# attiny_cortana.net
KiCad netlist of a schematic drawn in EAGLE
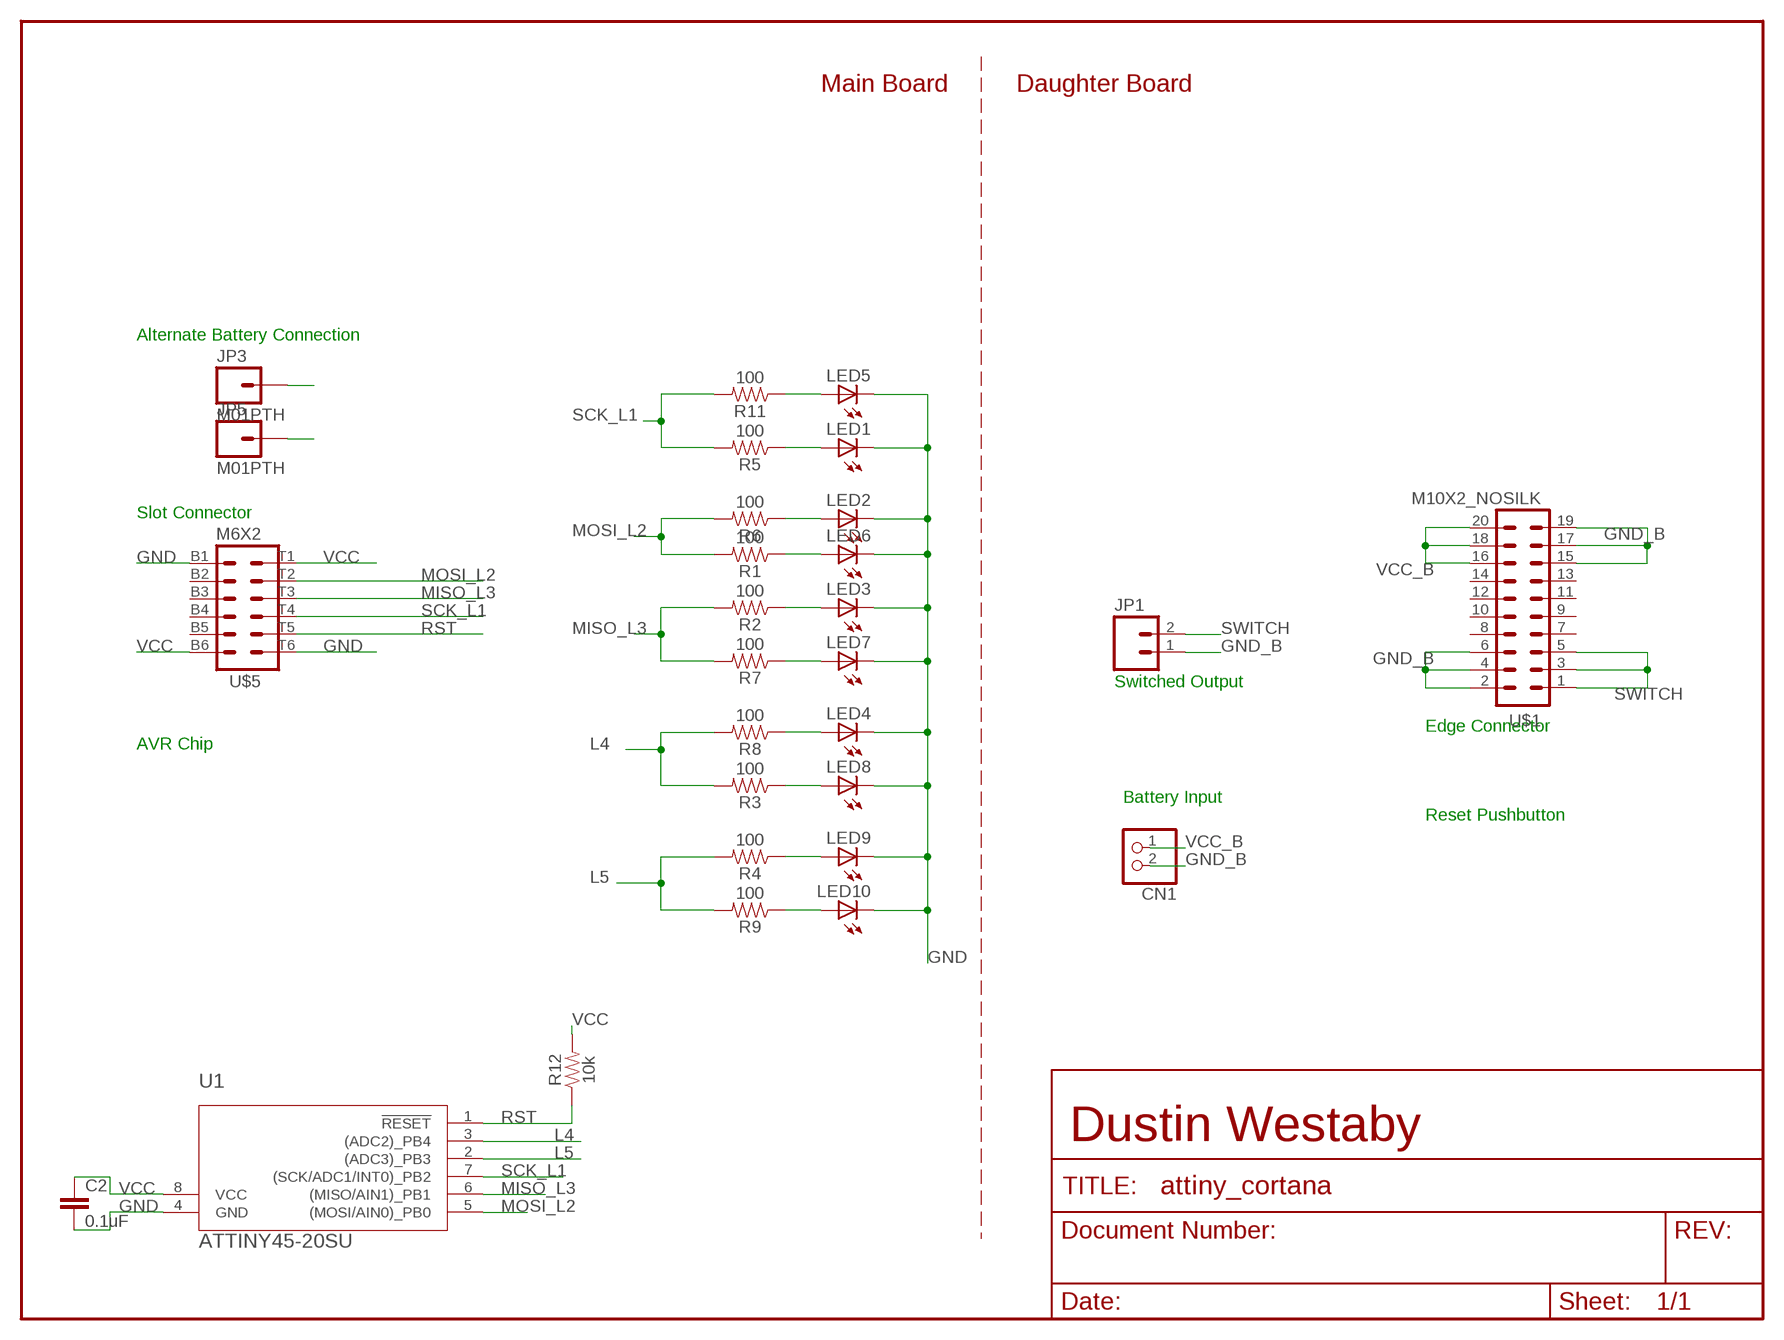
[diagram p0: schematic, sheet 1]

(export (version "E")
  (design (tool "Eeschema 10.0.6"))
  (components
    (comp (ref "C2")
      (value "0.1uF")
      (footprint "eagle-import:0402-TIGHT")
      (libsource (lib "eagle-import") (part "0.1UF-0402T-16V-10%"))
    )
    (comp (ref "CN1")
      (value "JST_2PIN-THM-RA")
      (footprint "eagle-import:JST-PH-2-THM-RA")
      (libsource (lib "eagle-import") (part "JST_2PIN-THM-RA"))
    )
    (comp (ref "JP1")
      (value "M02PTH")
      (footprint "eagle-import:1X02")
      (libsource (lib "eagle-import") (part "M02PTH"))
    )
    (comp (ref "JP3")
      (value "M01PTH")
      (footprint "eagle-import:1X01")
      (libsource (lib "eagle-import") (part "M01PTH"))
    )
    (comp (ref "JP5")
      (value "M01PTH")
      (footprint "eagle-import:1X01")
      (libsource (lib "eagle-import") (part "M01PTH"))
    )
    (comp (ref "LED1")
      (value "LED0603")
      (footprint "eagle-import:LED-0603")
      (libsource (lib "eagle-import") (part "LED0603"))
    )
    (comp (ref "LED2")
      (value "LED0603")
      (footprint "eagle-import:LED-0603")
      (libsource (lib "eagle-import") (part "LED0603"))
    )
    (comp (ref "LED3")
      (value "LED0603")
      (footprint "eagle-import:LED-0603")
      (libsource (lib "eagle-import") (part "LED0603"))
    )
    (comp (ref "LED4")
      (value "LED0603")
      (footprint "eagle-import:LED-0603")
      (libsource (lib "eagle-import") (part "LED0603"))
    )
    (comp (ref "LED5")
      (value "LED0603")
      (footprint "eagle-import:LED-0603")
      (libsource (lib "eagle-import") (part "LED0603"))
    )
    (comp (ref "LED6")
      (value "LED0603")
      (footprint "eagle-import:LED-0603")
      (libsource (lib "eagle-import") (part "LED0603"))
    )
    (comp (ref "LED7")
      (value "LED0603")
      (footprint "eagle-import:LED-0603")
      (libsource (lib "eagle-import") (part "LED0603"))
    )
    (comp (ref "LED8")
      (value "LED0603")
      (footprint "eagle-import:LED-0603")
      (libsource (lib "eagle-import") (part "LED0603"))
    )
    (comp (ref "LED9")
      (value "LED0603")
      (footprint "eagle-import:LED-0603")
      (libsource (lib "eagle-import") (part "LED0603"))
    )
    (comp (ref "LED10")
      (value "LED0603")
      (footprint "eagle-import:LED-0603")
      (libsource (lib "eagle-import") (part "LED0603"))
    )
    (comp (ref "R1")
      (value "100")
      (footprint "eagle-import:0402-TIGHT")
      (libsource (lib "eagle-import") (part "10KOHM-0402T-1/16W-1%"))
    )
    (comp (ref "R2")
      (value "100")
      (footprint "eagle-import:0402-TIGHT")
      (libsource (lib "eagle-import") (part "10KOHM-0402T-1/16W-1%"))
    )
    (comp (ref "R3")
      (value "100")
      (footprint "eagle-import:0402-TIGHT")
      (libsource (lib "eagle-import") (part "10KOHM-0402T-1/16W-1%"))
    )
    (comp (ref "R4")
      (value "100")
      (footprint "eagle-import:0402-TIGHT")
      (libsource (lib "eagle-import") (part "10KOHM-0402T-1/16W-1%"))
    )
    (comp (ref "R5")
      (value "100")
      (footprint "eagle-import:0402-TIGHT")
      (libsource (lib "eagle-import") (part "10KOHM-0402T-1/16W-1%"))
    )
    (comp (ref "R6")
      (value "100")
      (footprint "eagle-import:0402-TIGHT")
      (libsource (lib "eagle-import") (part "10KOHM-0402T-1/16W-1%"))
    )
    (comp (ref "R7")
      (value "100")
      (footprint "eagle-import:0402-TIGHT")
      (libsource (lib "eagle-import") (part "10KOHM-0402T-1/16W-1%"))
    )
    (comp (ref "R8")
      (value "100")
      (footprint "eagle-import:0402-TIGHT")
      (libsource (lib "eagle-import") (part "10KOHM-0402T-1/16W-1%"))
    )
    (comp (ref "R9")
      (value "100")
      (footprint "eagle-import:0402-TIGHT")
      (libsource (lib "eagle-import") (part "10KOHM-0402T-1/16W-1%"))
    )
    (comp (ref "R11")
      (value "100")
      (footprint "eagle-import:0402-TIGHT")
      (libsource (lib "eagle-import") (part "10KOHM-0402T-1/16W-1%"))
    )
    (comp (ref "R12")
      (value "10k")
      (footprint "eagle-import:0402-TIGHT")
      (libsource (lib "eagle-import") (part "10KOHM-0402T-1/16W-1%"))
    )
    (comp (ref "U$1")
      (value "M10X2_NOSILK")
      (footprint "eagle-import:2X10_NOSILK")
      (libsource (lib "eagle-import") (part "M10X2_NOSILK"))
    )
    (comp (ref "U$5")
      (value "M6X2")
      (footprint "eagle-import:CRT_CON")
      (libsource (lib "eagle-import") (part "M6X2"))
    )
    (comp (ref "U1")
      (value "ATTINY45-20SU")
      (footprint "eagle-import:8S2_ATM")
      (fields (field (name "COPYRIGHT") "Copyright (C) 2021 Ultra Librarian. All rights reserved."))
      (libsource (lib "eagle-import") (part "ATTINY45-20SU"))
    )
  )
  (nets
    (net (code "1") (name "/GND") (class "Default")
      (node (ref "C2") (pin "2") (pinfunction "2_2") (pintype "passive"))
      (node (ref "JP5") (pin "1") (pinfunction "1_1") (pintype "passive"))
      (node (ref "LED1") (pin "C") (pinfunction "C_C") (pintype "passive"))
      (node (ref "LED10") (pin "C") (pinfunction "C_C") (pintype "passive"))
      (node (ref "LED2") (pin "C") (pinfunction "C_C") (pintype "passive"))
      (node (ref "LED3") (pin "C") (pinfunction "C_C") (pintype "passive"))
      (node (ref "LED4") (pin "C") (pinfunction "C_C") (pintype "passive"))
      (node (ref "LED5") (pin "C") (pinfunction "C_C") (pintype "passive"))
      (node (ref "LED6") (pin "C") (pinfunction "C_C") (pintype "passive"))
      (node (ref "LED7") (pin "C") (pinfunction "C_C") (pintype "passive"))
      (node (ref "LED8") (pin "C") (pinfunction "C_C") (pintype "passive"))
      (node (ref "LED9") (pin "C") (pinfunction "C_C") (pintype "passive"))
      (node (ref "U$5") (pin "B1") (pinfunction "1_B1") (pintype "passive"))
      (node (ref "U$5") (pin "T6") (pinfunction "12_T6") (pintype "passive"))
      (node (ref "U1") (pin "4") (pinfunction "GND_4") (pintype "power_in"))
    )
    (net (code "2") (name "/GND_B") (class "Default")
      (node (ref "CN1") (pin "2") (pinfunction "1_2") (pintype "passive"))
      (node (ref "JP1") (pin "1") (pinfunction "1_1") (pintype "passive"))
      (node (ref "U$1") (pin "15") (pinfunction "15_15") (pintype "passive"))
      (node (ref "U$1") (pin "17") (pinfunction "17_17") (pintype "passive"))
      (node (ref "U$1") (pin "19") (pinfunction "19_19") (pintype "passive"))
      (node (ref "U$1") (pin "2") (pinfunction "2_2") (pintype "passive"))
      (node (ref "U$1") (pin "4") (pinfunction "4_4") (pintype "passive"))
      (node (ref "U$1") (pin "6") (pinfunction "6_6") (pintype "passive"))
    )
    (net (code "3") (name "/L4") (class "Default")
      (node (ref "R3") (pin "2") (pinfunction "2_2") (pintype "passive"))
      (node (ref "R8") (pin "2") (pinfunction "2_2") (pintype "passive"))
      (node (ref "U1") (pin "3") (pinfunction "(ADC2)_PB4_3") (pintype "bidirectional"))
    )
    (net (code "4") (name "/L5") (class "Default")
      (node (ref "R4") (pin "2") (pinfunction "2_2") (pintype "passive"))
      (node (ref "R9") (pin "2") (pinfunction "2_2") (pintype "passive"))
      (node (ref "U1") (pin "2") (pinfunction "(ADC3)_PB3_2") (pintype "bidirectional"))
    )
    (net (code "5") (name "/MISO_L3") (class "Default")
      (node (ref "R2") (pin "2") (pinfunction "2_2") (pintype "passive"))
      (node (ref "R7") (pin "2") (pinfunction "2_2") (pintype "passive"))
      (node (ref "U$5") (pin "T3") (pinfunction "9_T3") (pintype "passive"))
      (node (ref "U1") (pin "6") (pinfunction "(MISO/AIN1)_PB1_6") (pintype "bidirectional"))
    )
    (net (code "6") (name "/MOSI_L2") (class "Default")
      (node (ref "R1") (pin "2") (pinfunction "2_2") (pintype "passive"))
      (node (ref "R6") (pin "2") (pinfunction "2_2") (pintype "passive"))
      (node (ref "U$5") (pin "T2") (pinfunction "8_T2") (pintype "passive"))
      (node (ref "U1") (pin "5") (pinfunction "(MOSI/AIN0)_PB0_5") (pintype "bidirectional"))
    )
    (net (code "7") (name "/RST") (class "Default")
      (node (ref "R12") (pin "1") (pinfunction "1_1") (pintype "passive"))
      (node (ref "U$5") (pin "T5") (pinfunction "11_T5") (pintype "passive"))
      (node (ref "U1") (pin "1") (pinfunction "~{RESET}_1") (pintype "bidirectional"))
    )
    (net (code "8") (name "/SCK_L1") (class "Default")
      (node (ref "R11") (pin "2") (pinfunction "2_2") (pintype "passive"))
      (node (ref "R5") (pin "2") (pinfunction "2_2") (pintype "passive"))
      (node (ref "U$5") (pin "T4") (pinfunction "10_T4") (pintype "passive"))
      (node (ref "U1") (pin "7") (pinfunction "(SCK/ADC1/INT0)_PB2_7") (pintype "bidirectional"))
    )
    (net (code "9") (name "/SWITCH") (class "Default")
      (node (ref "JP1") (pin "2") (pinfunction "2_2") (pintype "passive"))
      (node (ref "U$1") (pin "1") (pinfunction "1_1") (pintype "passive"))
      (node (ref "U$1") (pin "3") (pinfunction "3_3") (pintype "passive"))
      (node (ref "U$1") (pin "5") (pinfunction "5_5") (pintype "passive"))
    )
    (net (code "10") (name "/VCC") (class "Default")
      (node (ref "C2") (pin "1") (pinfunction "1_1") (pintype "passive"))
      (node (ref "JP3") (pin "1") (pinfunction "1_1") (pintype "passive"))
      (node (ref "R12") (pin "2") (pinfunction "2_2") (pintype "passive"))
      (node (ref "U$5") (pin "B6") (pinfunction "6_B6") (pintype "passive"))
      (node (ref "U$5") (pin "T1") (pinfunction "7_T1") (pintype "passive"))
      (node (ref "U1") (pin "8") (pinfunction "VCC_8") (pintype "power_in"))
    )
    (net (code "11") (name "/VCC_B") (class "Default")
      (node (ref "CN1") (pin "1") (pinfunction "2_1") (pintype "passive"))
      (node (ref "U$1") (pin "16") (pinfunction "16_16") (pintype "passive"))
      (node (ref "U$1") (pin "18") (pinfunction "18_18") (pintype "passive"))
      (node (ref "U$1") (pin "20") (pinfunction "20_20") (pintype "passive"))
    )
    (net (code "12") (name "Net-(LED1-PadA)") (class "Default")
      (node (ref "LED1") (pin "A") (pinfunction "A_A") (pintype "passive"))
      (node (ref "R5") (pin "1") (pinfunction "1_1") (pintype "passive"))
    )
    (net (code "13") (name "Net-(LED2-PadA)") (class "Default")
      (node (ref "LED2") (pin "A") (pinfunction "A_A") (pintype "passive"))
      (node (ref "R6") (pin "1") (pinfunction "1_1") (pintype "passive"))
    )
    (net (code "14") (name "Net-(LED3-PadA)") (class "Default")
      (node (ref "LED3") (pin "A") (pinfunction "A_A") (pintype "passive"))
      (node (ref "R2") (pin "1") (pinfunction "1_1") (pintype "passive"))
    )
    (net (code "15") (name "Net-(LED4-PadA)") (class "Default")
      (node (ref "LED4") (pin "A") (pinfunction "A_A") (pintype "passive"))
      (node (ref "R8") (pin "1") (pinfunction "1_1") (pintype "passive"))
    )
    (net (code "16") (name "Net-(LED5-PadA)") (class "Default")
      (node (ref "LED5") (pin "A") (pinfunction "A_A") (pintype "passive"))
      (node (ref "R11") (pin "1") (pinfunction "1_1") (pintype "passive"))
    )
    (net (code "17") (name "Net-(LED6-PadA)") (class "Default")
      (node (ref "LED6") (pin "A") (pinfunction "A_A") (pintype "passive"))
      (node (ref "R1") (pin "1") (pinfunction "1_1") (pintype "passive"))
    )
    (net (code "18") (name "Net-(LED7-PadA)") (class "Default")
      (node (ref "LED7") (pin "A") (pinfunction "A_A") (pintype "passive"))
      (node (ref "R7") (pin "1") (pinfunction "1_1") (pintype "passive"))
    )
    (net (code "19") (name "Net-(LED8-PadA)") (class "Default")
      (node (ref "LED8") (pin "A") (pinfunction "A_A") (pintype "passive"))
      (node (ref "R3") (pin "1") (pinfunction "1_1") (pintype "passive"))
    )
    (net (code "20") (name "Net-(LED9-PadA)") (class "Default")
      (node (ref "LED9") (pin "A") (pinfunction "A_A") (pintype "passive"))
      (node (ref "R4") (pin "1") (pinfunction "1_1") (pintype "passive"))
    )
    (net (code "21") (name "Net-(LED10-PadA)") (class "Default")
      (node (ref "LED10") (pin "A") (pinfunction "A_A") (pintype "passive"))
      (node (ref "R9") (pin "1") (pinfunction "1_1") (pintype "passive"))
    )
    (net (code "22") (name "unconnected-(U$1-Pad7)") (class "Default")
      (node (ref "U$1") (pin "7") (pinfunction "7_7") (pintype "passive"))
    )
    (net (code "23") (name "unconnected-(U$1-Pad8)") (class "Default")
      (node (ref "U$1") (pin "8") (pinfunction "8_8") (pintype "passive"))
    )
    (net (code "24") (name "unconnected-(U$1-Pad9)") (class "Default")
      (node (ref "U$1") (pin "9") (pinfunction "9_9") (pintype "passive"))
    )
    (net (code "25") (name "unconnected-(U$1-Pad10)") (class "Default")
      (node (ref "U$1") (pin "10") (pinfunction "10_10") (pintype "passive"))
    )
    (net (code "26") (name "unconnected-(U$1-Pad11)") (class "Default")
      (node (ref "U$1") (pin "11") (pinfunction "11_11") (pintype "passive"))
    )
    (net (code "27") (name "unconnected-(U$1-Pad12)") (class "Default")
      (node (ref "U$1") (pin "12") (pinfunction "12_12") (pintype "passive"))
    )
    (net (code "28") (name "unconnected-(U$1-Pad13)") (class "Default")
      (node (ref "U$1") (pin "13") (pinfunction "13_13") (pintype "passive"))
    )
    (net (code "29") (name "unconnected-(U$1-Pad14)") (class "Default")
      (node (ref "U$1") (pin "14") (pinfunction "14_14") (pintype "passive"))
    )
    (net (code "30") (name "unconnected-(U$5-2-PadB2)") (class "Default")
      (node (ref "U$5") (pin "B2") (pinfunction "2_B2") (pintype "passive"))
    )
    (net (code "31") (name "unconnected-(U$5-3-PadB3)") (class "Default")
      (node (ref "U$5") (pin "B3") (pinfunction "3_B3") (pintype "passive"))
    )
    (net (code "32") (name "unconnected-(U$5-4-PadB4)") (class "Default")
      (node (ref "U$5") (pin "B4") (pinfunction "4_B4") (pintype "passive"))
    )
    (net (code "33") (name "unconnected-(U$5-5-PadB5)") (class "Default")
      (node (ref "U$5") (pin "B5") (pinfunction "5_B5") (pintype "passive"))
    )
  )
)
